# power.net
KiCad netlist of a schematic drawn in Altium Designer
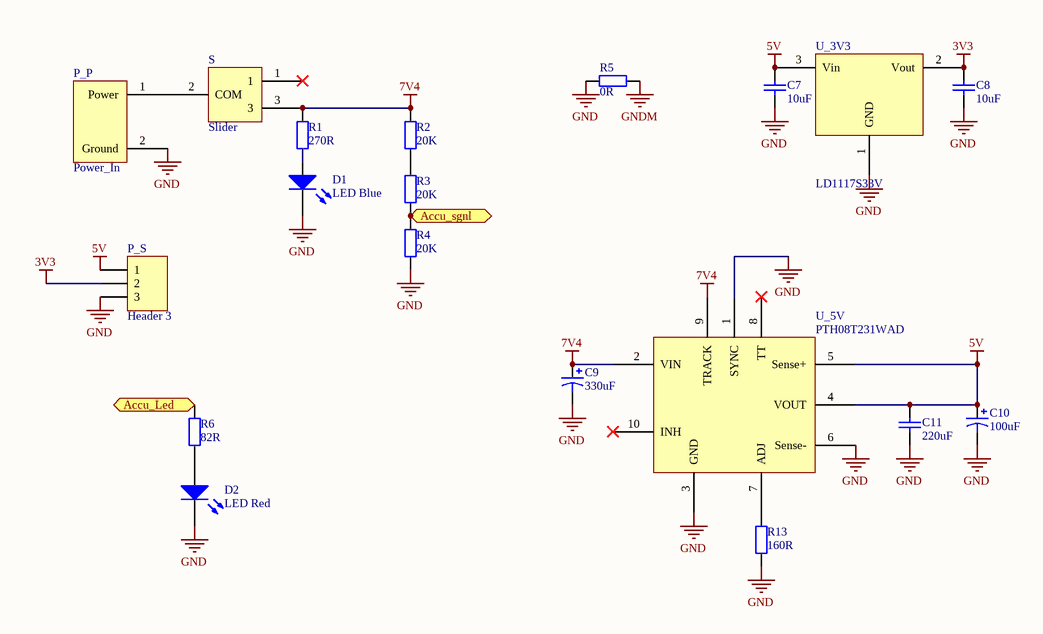
[diagram p0: power.SchDoc]

(export (version "E")
  (design (tool "Eeschema 10.0.6"))
  (components
    (comp (ref "C7")
      (value "10uF")
      (footprint "FP_0805_CAP_085")
      (description "Capacitor")
      (fields (field (name "TOLERANCE") "10%") (field (name "VOLTAGE") "16V"))
      (libsource (lib "hallglib") (part "CAP 10uF"))
    )
    (comp (ref "C8")
      (value "10uF")
      (footprint "FP_0805_CAP_085")
      (description "Capacitor")
      (fields (field (name "TOLERANCE") "10%") (field (name "VOLTAGE") "16V"))
      (libsource (lib "hallglib") (part "CAP 10uF"))
    )
    (comp (ref "C9")
      (value "330uF")
      (footprint "FP_7343")
      (description "Polarized Capacitor")
      (fields (field (name "VOLTAGE") "10V") (field (name "TOLERANCE") "20%"))
      (libsource (lib "hallglib") (part "CAP_ELECT"))
    )
    (comp (ref "C10")
      (value "100uF")
      (footprint "FP_3528")
      (description "Polarized Capacitor")
      (fields (field (name "VOLTAGE") "6.3V") (field (name "TOLERANCE") "10%"))
      (libsource (lib "hallglib") (part "CAP_ELECT"))
    )
    (comp (ref "C11")
      (value "220uF")
      (footprint "FP_1206_CAP_125")
      (description "Capacitor")
      (fields (field (name "TOLERANCE") "20%") (field (name "VOLTAGE") "6.3V"))
      (libsource (lib "hallglib") (part "CAP"))
    )
    (comp (ref "D1")
      (value "LED Blue")
      (footprint "FP_0805_LED_RED")
      (description "Blue LED")
      (libsource (lib "hallglib") (part "LED Blue"))
    )
    (comp (ref "D2")
      (value "LED Red")
      (footprint "FP_0805_LED_RED")
      (description "Red LED")
      (libsource (lib "hallglib") (part "LED Red"))
    )
    (comp (ref "P_P") (value "Power_In") (footprint "SORK.3.81mm") (libsource (lib "qlib") (part "Power_In")))
    (comp (ref "P_S")
      (value "Header 3")
      (footprint "HDR1X3")
      (description "Header, 3-Pin")
      (fields (field (name "PUBLISHER") "Altium Limited"))
      (libsource (lib "Miscellaneous Connectors") (part "Header 3"))
    )
    (comp (ref "R1")
      (value "270R")
      (footprint "FP_0805_RES")
      (description "Resistor")
      (fields (field (name "TOLERANCE") "5%") (field (name "POWER") "125mW"))
      (libsource (lib "hallglib") (part "RES 270R"))
    )
    (comp (ref "R2")
      (value "20K")
      (footprint "FP_0805_RES")
      (description "Resistor")
      (fields (field (name "TOLERANCE") "1%") (field (name "POWER") "0.125W"))
      (libsource (lib "hallglib") (part "RES"))
    )
    (comp (ref "R3")
      (value "20K")
      (footprint "FP_0805_RES")
      (description "Resistor")
      (fields (field (name "TOLERANCE") "1%") (field (name "POWER") "0.125W"))
      (libsource (lib "hallglib") (part "RES"))
    )
    (comp (ref "R4")
      (value "20K")
      (footprint "FP_0805_RES")
      (description "Resistor")
      (fields (field (name "TOLERANCE") "1%") (field (name "POWER") "0.125W"))
      (libsource (lib "hallglib") (part "RES"))
    )
    (comp (ref "R5")
      (value "0R")
      (footprint "FP_0805_RES")
      (description "Resistor")
      (fields (field (name "POWER") "0.125W"))
      (libsource (lib "") (part "RES_1"))
    )
    (comp (ref "R6")
      (value "82R")
      (footprint "FP_0805_RES")
      (description "Resistor")
      (fields (field (name "TOLERANCE") "5%") (field (name "POWER") "125mW"))
      (libsource (lib "hallglib") (part "RES 82R"))
    )
    (comp (ref "R13")
      (value "160R")
      (footprint "FP_0805_RES")
      (description "Resistor")
      (fields (field (name "TOLERANCE") "1%") (field (name "POWER") "0.125W"))
      (libsource (lib "hallglib") (part "RES"))
    )
    (comp (ref "S") (value "Slider") (footprint "Slide") (libsource (lib "qlib") (part "Slider")))
    (comp (ref "U_3V3")
      (value "LD1117S33V")
      (footprint "FP_SOT223")
      (libsource (lib "qlib") (part "LD1117S33V"))
    )
    (comp (ref "U_5V")
      (value "PTH08T231WAD")
      (footprint "5V SUPPLY")
      (libsource (lib "qlib") (part "5V_SUPPLY"))
    )
  )
  (nets
    (net (code "1") (name "/Accu_Led") (class "Default")
      (node (ref "R6") (pin "2") (pinfunction "2_2") (pintype "passive"))
    )
    (net (code "2") (name "/Accu_sgnl") (class "Default")
      (node (ref "R3") (pin "1") (pinfunction "1_1") (pintype "passive"))
      (node (ref "R4") (pin "2") (pinfunction "2_2") (pintype "passive"))
    )
    (net (code "3") (name "3V3") (class "Default")
      (node (ref "C8") (pin "2") (pinfunction "2_2") (pintype "passive"))
      (node (ref "P_S") (pin "2") (pinfunction "2_2") (pintype "passive"))
      (node (ref "U_3V3") (pin "2") (pinfunction "Vout_2") (pintype "passive"))
    )
    (net (code "4") (name "5V") (class "Default")
      (node (ref "C10") (pin "P") (pinfunction "P_P") (pintype "passive"))
      (node (ref "C11") (pin "2") (pinfunction "2_2") (pintype "passive"))
      (node (ref "C7") (pin "2") (pinfunction "2_2") (pintype "passive"))
      (node (ref "P_S") (pin "1") (pinfunction "1_1") (pintype "passive"))
      (node (ref "U_3V3") (pin "3") (pinfunction "Vin_3") (pintype "passive"))
      (node (ref "U_5V") (pin "4") (pinfunction "VOUT_4") (pintype "passive"))
      (node (ref "U_5V") (pin "5") (pinfunction "Sense+_5") (pintype "passive"))
    )
    (net (code "5") (name "7V4") (class "Default")
      (node (ref "C9") (pin "P") (pinfunction "P_P") (pintype "passive"))
      (node (ref "R1") (pin "2") (pinfunction "2_2") (pintype "passive"))
      (node (ref "R2") (pin "2") (pinfunction "2_2") (pintype "passive"))
      (node (ref "S") (pin "3") (pinfunction "3_3") (pintype "passive"))
      (node (ref "U_5V") (pin "2") (pinfunction "VIN_2") (pintype "passive"))
      (node (ref "U_5V") (pin "9") (pinfunction "TRACK_9") (pintype "passive"))
    )
    (net (code "6") (name "GND") (class "Default")
      (node (ref "C10") (pin "N") (pinfunction "N_N") (pintype "passive"))
      (node (ref "C11") (pin "1") (pinfunction "1_1") (pintype "passive"))
      (node (ref "C7") (pin "1") (pinfunction "1_1") (pintype "passive"))
      (node (ref "C8") (pin "1") (pinfunction "1_1") (pintype "passive"))
      (node (ref "C9") (pin "N") (pinfunction "N_N") (pintype "passive"))
      (node (ref "D1") (pin "2") (pinfunction "K_2") (pintype "passive"))
      (node (ref "D2") (pin "2") (pinfunction "K_2") (pintype "passive"))
      (node (ref "P_P") (pin "2") (pinfunction "Ground_2") (pintype "passive"))
      (node (ref "P_S") (pin "3") (pinfunction "3_3") (pintype "passive"))
      (node (ref "R13") (pin "1") (pinfunction "1_1") (pintype "passive"))
      (node (ref "R4") (pin "1") (pinfunction "1_1") (pintype "passive"))
      (node (ref "R5") (pin "1") (pinfunction "1_1") (pintype "passive"))
      (node (ref "U_3V3") (pin "1") (pinfunction "GND_1") (pintype "passive"))
      (node (ref "U_5V") (pin "1") (pinfunction "SYNC_1") (pintype "passive"))
      (node (ref "U_5V") (pin "3") (pinfunction "GND_3") (pintype "passive"))
      (node (ref "U_5V") (pin "6") (pinfunction "Sense-_6") (pintype "passive"))
    )
    (net (code "7") (name "GNDM") (class "Default")
      (node (ref "R5") (pin "2") (pinfunction "2_2") (pintype "passive"))
    )
    (net (code "8") (name "Net-(D1-A)") (class "Default")
      (node (ref "D1") (pin "1") (pinfunction "A_1") (pintype "passive"))
      (node (ref "R1") (pin "1") (pinfunction "1_1") (pintype "passive"))
    )
    (net (code "9") (name "Net-(D2-A)") (class "Default")
      (node (ref "D2") (pin "1") (pinfunction "A_1") (pintype "passive"))
      (node (ref "R6") (pin "1") (pinfunction "1_1") (pintype "passive"))
    )
    (net (code "10") (name "Net-(P_P-Power)") (class "Default")
      (node (ref "P_P") (pin "1") (pinfunction "Power_1") (pintype "passive"))
      (node (ref "S") (pin "2") (pinfunction "COM_2") (pintype "passive"))
    )
    (net (code "11") (name "Net-(R2-Pad1)") (class "Default")
      (node (ref "R2") (pin "1") (pinfunction "1_1") (pintype "passive"))
      (node (ref "R3") (pin "2") (pinfunction "2_2") (pintype "passive"))
    )
    (net (code "12") (name "Net-(U_5V-ADJ)") (class "Default")
      (node (ref "R13") (pin "2") (pinfunction "2_2") (pintype "passive"))
      (node (ref "U_5V") (pin "7") (pinfunction "ADJ_7") (pintype "passive"))
    )
    (net (code "13") (name "unconnected-(S-Pad1)") (class "Default")
      (node (ref "S") (pin "1") (pinfunction "1_1") (pintype "passive+no_connect"))
    )
    (net (code "14") (name "unconnected-(U_5V-INH-Pad10)") (class "Default")
      (node (ref "U_5V") (pin "10") (pinfunction "INH_10") (pintype "passive+no_connect"))
    )
    (net (code "15") (name "unconnected-(U_5V-TT-Pad8)") (class "Default")
      (node (ref "U_5V") (pin "8") (pinfunction "TT_8") (pintype "passive+no_connect"))
    )
  )
)
